# power-supply.net
KiCad netlist of a schematic drawn in EAGLE
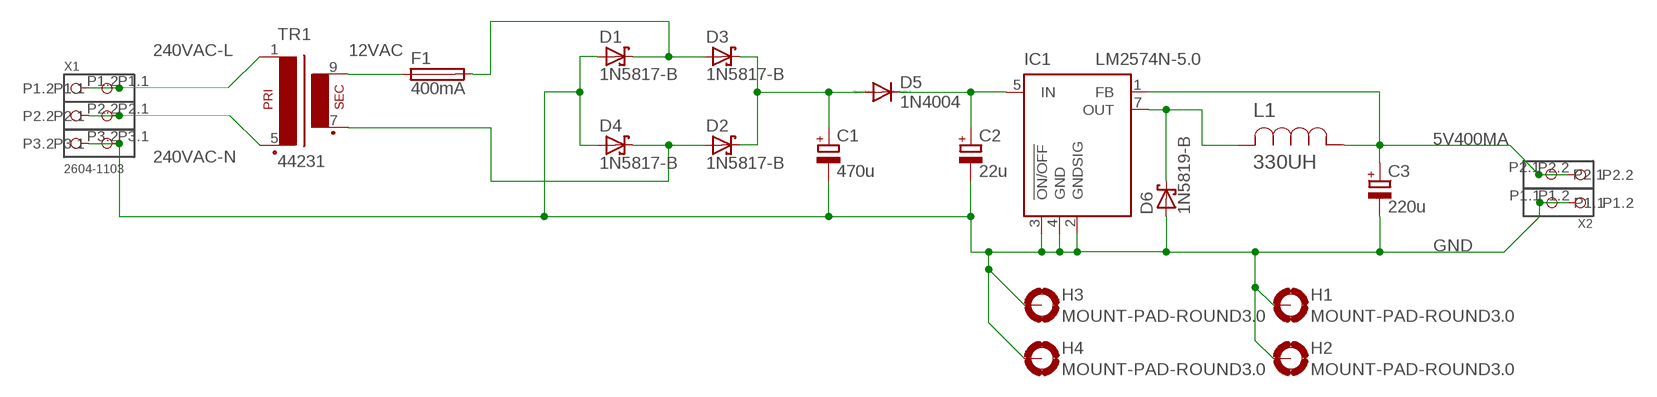
[diagram p0: schematic, sheet 1]

(export (version "E")
  (design (tool "Eeschema 10.0.6"))
  (components
    (comp (ref "C1")
      (value "470u")
      (footprint "eagle-import:E3,5-8")
      (libsource (lib "eagle-import") (part "CPOL-EUE3.5-8"))
    )
    (comp (ref "C2")
      (value "22u")
      (footprint "eagle-import:E2-4")
      (libsource (lib "eagle-import") (part "CPOL-EUE2-4"))
    )
    (comp (ref "C3")
      (value "220u")
      (footprint "eagle-import:E2-5")
      (libsource (lib "eagle-import") (part "CPOL-EUE2-5"))
    )
    (comp (ref "D1")
      (value "1N5817-B")
      (footprint "eagle-import:DO41-7.6")
      (libsource (lib "eagle-import") (part "1N5817-B"))
    )
    (comp (ref "D2")
      (value "1N5817-B")
      (footprint "eagle-import:DO41-7.6")
      (libsource (lib "eagle-import") (part "1N5817-B"))
    )
    (comp (ref "D3")
      (value "1N5817-B")
      (footprint "eagle-import:DO41-7.6")
      (libsource (lib "eagle-import") (part "1N5817-B"))
    )
    (comp (ref "D4")
      (value "1N5817-B")
      (footprint "eagle-import:DO41-7.6")
      (libsource (lib "eagle-import") (part "1N5817-B"))
    )
    (comp (ref "D5")
      (value "1N4004")
      (footprint "eagle-import:DO41-10")
      (libsource (lib "eagle-import") (part "1N4004"))
    )
    (comp (ref "D6")
      (value "1N5819-B")
      (footprint "eagle-import:DO41-7.6")
      (libsource (lib "eagle-import") (part "1N5819-B"))
    )
    (comp (ref "F1")
      (value "400mA")
      (footprint "eagle-import:SH22,5")
      (fields (field (name "MF") "SCHURTER") (field (name "MPN") "0031.8201"))
      (libsource (lib "eagle-import") (part "SH22,5"))
    )
    (comp (ref "H1")
      (value "MOUNT-PAD-ROUND3.0")
      (footprint "eagle-import:3,0-PAD")
      (libsource (lib "eagle-import") (part "MOUNT-PAD-ROUND3.0"))
    )
    (comp (ref "H2")
      (value "MOUNT-PAD-ROUND3.0")
      (footprint "eagle-import:3,0-PAD")
      (libsource (lib "eagle-import") (part "MOUNT-PAD-ROUND3.0"))
    )
    (comp (ref "H3")
      (value "MOUNT-PAD-ROUND3.0")
      (footprint "eagle-import:3,0-PAD")
      (libsource (lib "eagle-import") (part "MOUNT-PAD-ROUND3.0"))
    )
    (comp (ref "H4")
      (value "MOUNT-PAD-ROUND3.0")
      (footprint "eagle-import:3,0-PAD")
      (libsource (lib "eagle-import") (part "MOUNT-PAD-ROUND3.0"))
    )
    (comp (ref "IC1")
      (value "LM2574N-5.0")
      (footprint "eagle-import:DIL08")
      (libsource (lib "eagle-import") (part "LM2574?-N5.0"))
    )
    (comp (ref "L1")
      (value "330UH")
      (footprint "eagle-import:IND_ELC11D")
      (fields (field (name "MPN") "ELC11D331F"))
      (libsource (lib "eagle-import") (part "ELC-11D11D331F"))
    )
    (comp (ref "TR1")
      (value "44231")
      (footprint "eagle-import:EI42-1")
      (libsource (lib "eagle-import") (part "EI42-1"))
    )
    (comp (ref "X1")
      (value "2604-1103")
      (footprint "eagle-import:P-2604-1103")
      (libsource (lib "eagle-import") (part "2604-1103"))
    )
    (comp (ref "X2")
      (value "2604-1102")
      (footprint "eagle-import:P-2604-1102")
      (libsource (lib "eagle-import") (part "2604-1102"))
    )
  )
  (nets
    (net (code "1") (name "/5V400MA") (class "Default")
      (node (ref "C3") (pin "+") (pinfunction "+_+") (pintype "passive"))
      (node (ref "IC1") (pin "1") (pinfunction "FB_1") (pintype "input"))
      (node (ref "L1") (pin "1") (pinfunction "1_1") (pintype "passive"))
      (node (ref "X2") (pin "P2.1") (pinfunction "P2.1_P2.1") (pintype "bidirectional"))
      (node (ref "X2") (pin "P2.2") (pinfunction "P2.2_P2.2") (pintype "bidirectional"))
    )
    (net (code "2") (name "/12VAC") (class "Default")
      (node (ref "F1") (pin "1") (pinfunction "1_1") (pintype "passive"))
      (node (ref "TR1") (pin "9") (pinfunction "S4_9") (pintype "passive"))
    )
    (net (code "3") (name "/240VAC-L") (class "Default")
      (node (ref "TR1") (pin "1") (pinfunction "P1_1") (pintype "passive"))
      (node (ref "X1") (pin "P1.1") (pinfunction "P1.1_P1.1") (pintype "bidirectional"))
      (node (ref "X1") (pin "P1.2") (pinfunction "P1.2_P1.2") (pintype "bidirectional"))
    )
    (net (code "4") (name "/240VAC-N") (class "Default")
      (node (ref "TR1") (pin "5") (pinfunction "P2_5") (pintype "passive"))
      (node (ref "X1") (pin "P2.1") (pinfunction "P2.1_P2.1") (pintype "bidirectional"))
      (node (ref "X1") (pin "P2.2") (pinfunction "P2.2_P2.2") (pintype "bidirectional"))
    )
    (net (code "5") (name "/GND") (class "Default")
      (node (ref "C1") (pin "-") (pinfunction "-_-") (pintype "passive"))
      (node (ref "C2") (pin "-") (pinfunction "-_-") (pintype "passive"))
      (node (ref "C3") (pin "-") (pinfunction "-_-") (pintype "passive"))
      (node (ref "D1") (pin "A") (pinfunction "A_A") (pintype "passive"))
      (node (ref "D4") (pin "A") (pinfunction "A_A") (pintype "passive"))
      (node (ref "D6") (pin "A") (pinfunction "A_A") (pintype "passive"))
      (node (ref "H1") (pin "B3,0") (pinfunction "MOUNT_B3,0") (pintype "passive"))
      (node (ref "H2") (pin "B3,0") (pinfunction "MOUNT_B3,0") (pintype "passive"))
      (node (ref "H3") (pin "B3,0") (pinfunction "MOUNT_B3,0") (pintype "passive"))
      (node (ref "H4") (pin "B3,0") (pinfunction "MOUNT_B3,0") (pintype "passive"))
      (node (ref "IC1") (pin "2") (pinfunction "GNDSIG_2") (pintype "input"))
      (node (ref "IC1") (pin "3") (pinfunction "~{ON/OFF}_3") (pintype "input"))
      (node (ref "IC1") (pin "4") (pinfunction "GND_4") (pintype "power_in"))
      (node (ref "X1") (pin "P3.1") (pinfunction "P3.1_P3.1") (pintype "bidirectional"))
      (node (ref "X1") (pin "P3.2") (pinfunction "P3.2_P3.2") (pintype "bidirectional"))
      (node (ref "X2") (pin "P1.1") (pinfunction "P1.1_P1.1") (pintype "bidirectional"))
      (node (ref "X2") (pin "P1.2") (pinfunction "P1.2_P1.2") (pintype "bidirectional"))
    )
    (net (code "6") (name "Net-(C1-Pad+)") (class "Default")
      (node (ref "C1") (pin "+") (pinfunction "+_+") (pintype "passive"))
      (node (ref "D2") (pin "C") (pinfunction "C_C") (pintype "passive"))
      (node (ref "D3") (pin "C") (pinfunction "C_C") (pintype "passive"))
      (node (ref "D5") (pin "A") (pinfunction "A_A") (pintype "passive"))
    )
    (net (code "7") (name "Net-(D1-PadC)") (class "Default")
      (node (ref "D1") (pin "C") (pinfunction "C_C") (pintype "passive"))
      (node (ref "D3") (pin "A") (pinfunction "A_A") (pintype "passive"))
      (node (ref "F1") (pin "2") (pinfunction "2_2") (pintype "passive"))
    )
    (net (code "8") (name "Net-(IC1-IN)") (class "Default")
      (node (ref "C2") (pin "+") (pinfunction "+_+") (pintype "passive"))
      (node (ref "D5") (pin "C") (pinfunction "C_C") (pintype "passive"))
      (node (ref "IC1") (pin "5") (pinfunction "IN_5") (pintype "input"))
    )
    (net (code "9") (name "Net-(IC1-OUT)") (class "Default")
      (node (ref "D6") (pin "C") (pinfunction "C_C") (pintype "passive"))
      (node (ref "IC1") (pin "7") (pinfunction "OUT_7") (pintype "passive"))
      (node (ref "L1") (pin "2") (pinfunction "2_2") (pintype "passive"))
    )
    (net (code "10") (name "Net-(TR1-S3)") (class "Default")
      (node (ref "D2") (pin "A") (pinfunction "A_A") (pintype "passive"))
      (node (ref "D4") (pin "C") (pinfunction "C_C") (pintype "passive"))
      (node (ref "TR1") (pin "7") (pinfunction "S3_7") (pintype "passive"))
    )
  )
)
